# TOP.net
KiCad netlist of a schematic drawn in Altium Designer
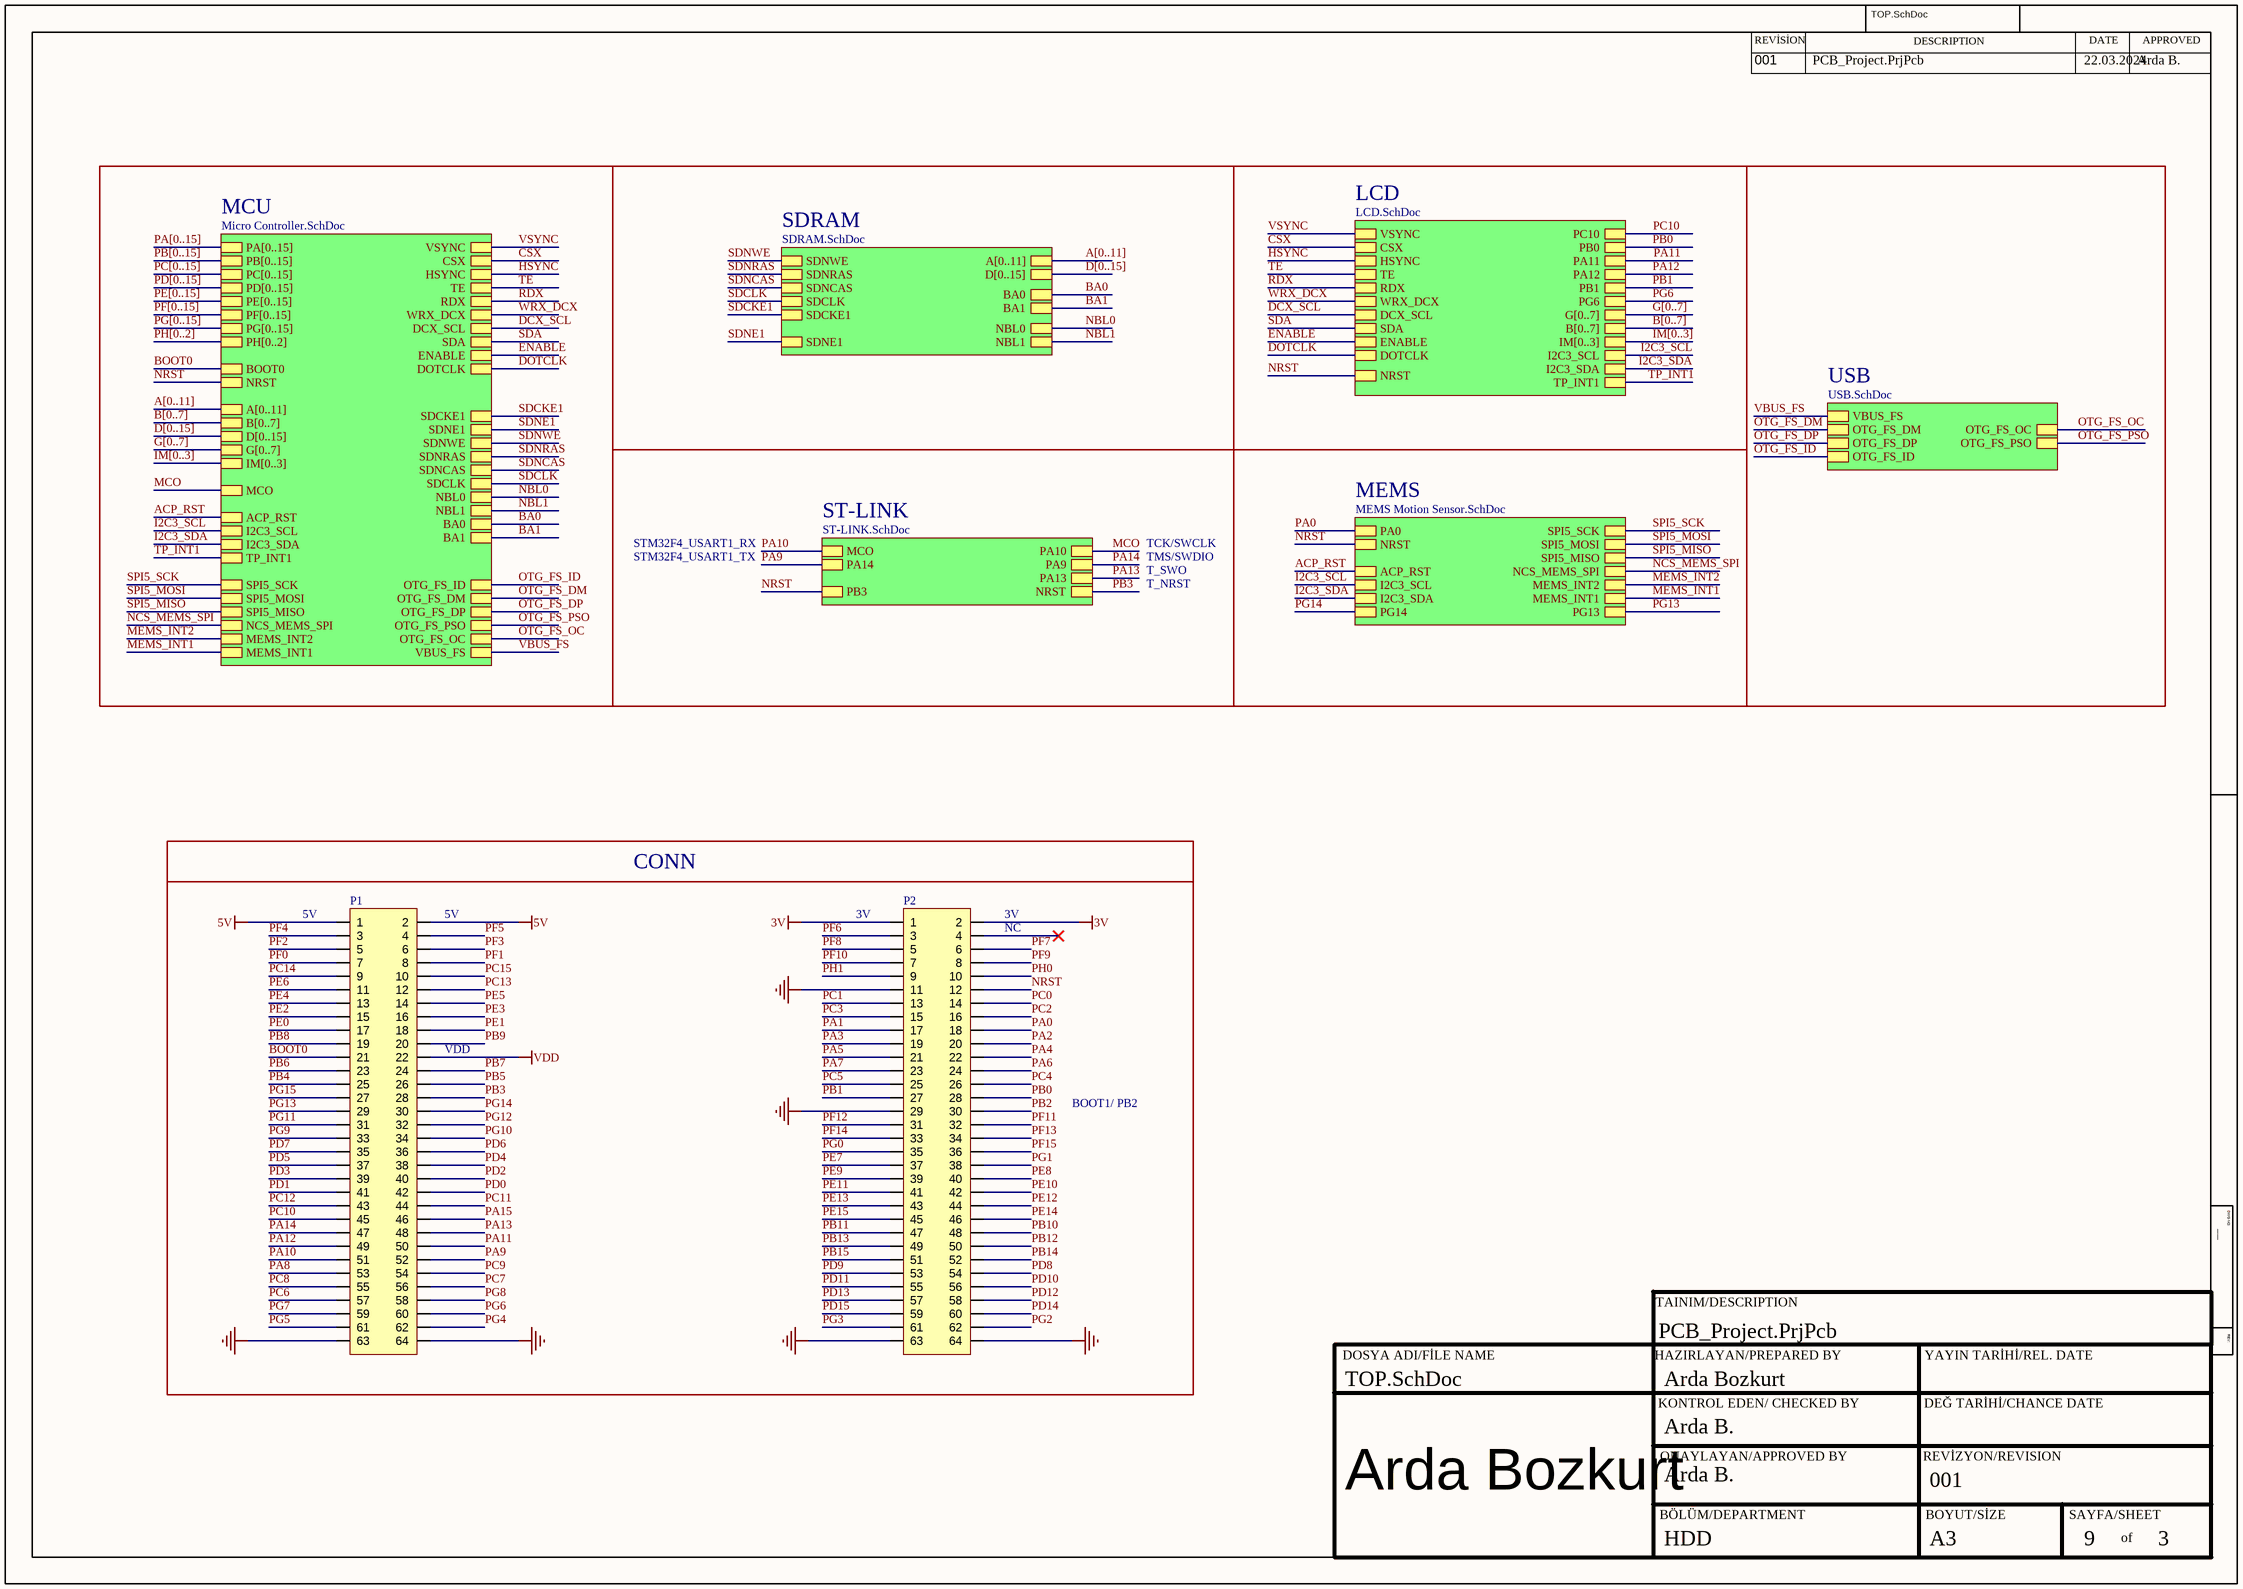
[diagram p0: TOP.SchDoc]

(export (version "E")
  (design (tool "Eeschema 10.0.6"))
  (components
    (comp (ref "P1")
      (value "TSW-132-24-T-D")
      (footprint "CONN-2*32POS")
      (description "Headers & Wire Housings Classic PCB Header Strips, 0.100 pitch")
      (fields
        (field (name "MANUFACTURER") "Wurth Electronics")
        (field (name "MANUFACTURER PART NUMBER") "61303221121")
      )
      (libsource (lib "STM32") (part "CONN HEADER VERT 32POS 2.54MM"))
    )
    (comp (ref "P2")
      (value "TSW-132-24-T-D")
      (footprint "CONN-2*32POS")
      (description "Headers & Wire Housings Classic PCB Header Strips, 0.100 pitch")
      (fields
        (field (name "MANUFACTURER") "Wurth Electronics")
        (field (name "MANUFACTURER PART NUMBER") "61303221121")
      )
      (libsource (lib "STM32") (part "CONN HEADER VERT 32POS 2.54MM"))
    )
  )
  (nets
    (net (code "54") (name "/BOOT0") (class "Default")
      (node (ref "P1") (pin "21") (pinfunction "21_21") (pintype "passive"))
    )
    (net (code "72") (name "/NRST") (class "Default")
      (node (ref "P2") (pin "12") (pinfunction "12_12") (pintype "passive"))
    )
    (net (code "78") (name "/PA0") (class "Default")
      (node (ref "P2") (pin "18") (pinfunction "18_18") (pintype "passive"))
    )
    (net (code "79") (name "/PA1") (class "Default")
      (node (ref "P2") (pin "17") (pinfunction "17_17") (pintype "passive"))
    )
    (net (code "80") (name "/PA2") (class "Default")
      (node (ref "P2") (pin "20") (pinfunction "20_20") (pintype "passive"))
    )
    (net (code "81") (name "/PA3") (class "Default")
      (node (ref "P2") (pin "19") (pinfunction "19_19") (pintype "passive"))
    )
    (net (code "82") (name "/PA4") (class "Default")
      (node (ref "P2") (pin "22") (pinfunction "22_22") (pintype "passive"))
    )
    (net (code "83") (name "/PA5") (class "Default")
      (node (ref "P2") (pin "21") (pinfunction "21_21") (pintype "passive"))
    )
    (net (code "84") (name "/PA6") (class "Default")
      (node (ref "P2") (pin "24") (pinfunction "24_24") (pintype "passive"))
    )
    (net (code "85") (name "/PA7") (class "Default")
      (node (ref "P2") (pin "23") (pinfunction "23_23") (pintype "passive"))
    )
    (net (code "86") (name "/PA8") (class "Default")
      (node (ref "P1") (pin "53") (pinfunction "53_53") (pintype "passive"))
    )
    (net (code "87") (name "/PA9") (class "Default")
      (node (ref "P1") (pin "52") (pinfunction "52_52") (pintype "passive"))
    )
    (net (code "88") (name "/PA10") (class "Default")
      (node (ref "P1") (pin "51") (pinfunction "51_51") (pintype "passive"))
    )
    (net (code "89") (name "/PA11") (class "Default")
      (node (ref "P1") (pin "50") (pinfunction "50_50") (pintype "passive"))
    )
    (net (code "90") (name "/PA12") (class "Default")
      (node (ref "P1") (pin "49") (pinfunction "49_49") (pintype "passive"))
    )
    (net (code "91") (name "/PA13") (class "Default")
      (node (ref "P1") (pin "48") (pinfunction "48_48") (pintype "passive"))
    )
    (net (code "92") (name "/PA14") (class "Default")
      (node (ref "P1") (pin "47") (pinfunction "47_47") (pintype "passive"))
    )
    (net (code "93") (name "/PA15") (class "Default")
      (node (ref "P1") (pin "46") (pinfunction "46_46") (pintype "passive"))
    )
    (net (code "95") (name "/PB0") (class "Default")
      (node (ref "P2") (pin "28") (pinfunction "28_28") (pintype "passive"))
    )
    (net (code "96") (name "/PB1") (class "Default")
      (node (ref "P2") (pin "27") (pinfunction "27_27") (pintype "passive"))
    )
    (net (code "97") (name "/PB2") (class "Default")
      (node (ref "P2") (pin "30") (pinfunction "30_30") (pintype "passive"))
    )
    (net (code "98") (name "/PB3") (class "Default")
      (node (ref "P1") (pin "28") (pinfunction "28_28") (pintype "passive"))
    )
    (net (code "99") (name "/PB4") (class "Default")
      (node (ref "P1") (pin "25") (pinfunction "25_25") (pintype "passive"))
    )
    (net (code "100") (name "/PB5") (class "Default")
      (node (ref "P1") (pin "26") (pinfunction "26_26") (pintype "passive"))
    )
    (net (code "101") (name "/PB6") (class "Default")
      (node (ref "P1") (pin "23") (pinfunction "23_23") (pintype "passive"))
    )
    (net (code "102") (name "/PB7") (class "Default")
      (node (ref "P1") (pin "24") (pinfunction "24_24") (pintype "passive"))
    )
    (net (code "103") (name "/PB8") (class "Default")
      (node (ref "P1") (pin "19") (pinfunction "19_19") (pintype "passive"))
    )
    (net (code "104") (name "/PB9") (class "Default")
      (node (ref "P1") (pin "20") (pinfunction "20_20") (pintype "passive"))
    )
    (net (code "105") (name "/PB10") (class "Default")
      (node (ref "P2") (pin "48") (pinfunction "48_48") (pintype "passive"))
    )
    (net (code "106") (name "/PB11") (class "Default")
      (node (ref "P2") (pin "47") (pinfunction "47_47") (pintype "passive"))
    )
    (net (code "107") (name "/PB12") (class "Default")
      (node (ref "P2") (pin "50") (pinfunction "50_50") (pintype "passive"))
    )
    (net (code "108") (name "/PB13") (class "Default")
      (node (ref "P2") (pin "49") (pinfunction "49_49") (pintype "passive"))
    )
    (net (code "109") (name "/PB14") (class "Default")
      (node (ref "P2") (pin "52") (pinfunction "52_52") (pintype "passive"))
    )
    (net (code "110") (name "/PB15") (class "Default")
      (node (ref "P2") (pin "51") (pinfunction "51_51") (pintype "passive"))
    )
    (net (code "112") (name "/PC0") (class "Default")
      (node (ref "P2") (pin "14") (pinfunction "14_14") (pintype "passive"))
    )
    (net (code "113") (name "/PC1") (class "Default")
      (node (ref "P2") (pin "13") (pinfunction "13_13") (pintype "passive"))
    )
    (net (code "114") (name "/PC2") (class "Default")
      (node (ref "P2") (pin "16") (pinfunction "16_16") (pintype "passive"))
    )
    (net (code "115") (name "/PC3") (class "Default")
      (node (ref "P2") (pin "15") (pinfunction "15_15") (pintype "passive"))
    )
    (net (code "116") (name "/PC4") (class "Default")
      (node (ref "P2") (pin "26") (pinfunction "26_26") (pintype "passive"))
    )
    (net (code "117") (name "/PC5") (class "Default")
      (node (ref "P2") (pin "25") (pinfunction "25_25") (pintype "passive"))
    )
    (net (code "118") (name "/PC6") (class "Default")
      (node (ref "P1") (pin "57") (pinfunction "57_57") (pintype "passive"))
    )
    (net (code "119") (name "/PC7") (class "Default")
      (node (ref "P1") (pin "56") (pinfunction "56_56") (pintype "passive"))
    )
    (net (code "120") (name "/PC8") (class "Default")
      (node (ref "P1") (pin "55") (pinfunction "55_55") (pintype "passive"))
    )
    (net (code "121") (name "/PC9") (class "Default")
      (node (ref "P1") (pin "54") (pinfunction "54_54") (pintype "passive"))
    )
    (net (code "122") (name "/PC10") (class "Default")
      (node (ref "P1") (pin "45") (pinfunction "45_45") (pintype "passive"))
    )
    (net (code "123") (name "/PC11") (class "Default")
      (node (ref "P1") (pin "44") (pinfunction "44_44") (pintype "passive"))
    )
    (net (code "124") (name "/PC12") (class "Default")
      (node (ref "P1") (pin "43") (pinfunction "43_43") (pintype "passive"))
    )
    (net (code "125") (name "/PC13") (class "Default")
      (node (ref "P1") (pin "12") (pinfunction "12_12") (pintype "passive"))
    )
    (net (code "126") (name "/PC14") (class "Default")
      (node (ref "P1") (pin "9") (pinfunction "9_9") (pintype "passive"))
    )
    (net (code "127") (name "/PC15") (class "Default")
      (node (ref "P1") (pin "10") (pinfunction "10_10") (pintype "passive"))
    )
    (net (code "129") (name "/PD0") (class "Default")
      (node (ref "P1") (pin "42") (pinfunction "42_42") (pintype "passive"))
    )
    (net (code "130") (name "/PD1") (class "Default")
      (node (ref "P1") (pin "41") (pinfunction "41_41") (pintype "passive"))
    )
    (net (code "131") (name "/PD2") (class "Default")
      (node (ref "P1") (pin "40") (pinfunction "40_40") (pintype "passive"))
    )
    (net (code "132") (name "/PD3") (class "Default")
      (node (ref "P1") (pin "39") (pinfunction "39_39") (pintype "passive"))
    )
    (net (code "133") (name "/PD4") (class "Default")
      (node (ref "P1") (pin "38") (pinfunction "38_38") (pintype "passive"))
    )
    (net (code "134") (name "/PD5") (class "Default")
      (node (ref "P1") (pin "37") (pinfunction "37_37") (pintype "passive"))
    )
    (net (code "135") (name "/PD6") (class "Default")
      (node (ref "P1") (pin "36") (pinfunction "36_36") (pintype "passive"))
    )
    (net (code "136") (name "/PD7") (class "Default")
      (node (ref "P1") (pin "35") (pinfunction "35_35") (pintype "passive"))
    )
    (net (code "137") (name "/PD8") (class "Default")
      (node (ref "P2") (pin "54") (pinfunction "54_54") (pintype "passive"))
    )
    (net (code "138") (name "/PD9") (class "Default")
      (node (ref "P2") (pin "53") (pinfunction "53_53") (pintype "passive"))
    )
    (net (code "139") (name "/PD10") (class "Default")
      (node (ref "P2") (pin "56") (pinfunction "56_56") (pintype "passive"))
    )
    (net (code "140") (name "/PD11") (class "Default")
      (node (ref "P2") (pin "55") (pinfunction "55_55") (pintype "passive"))
    )
    (net (code "141") (name "/PD12") (class "Default")
      (node (ref "P2") (pin "58") (pinfunction "58_58") (pintype "passive"))
    )
    (net (code "142") (name "/PD13") (class "Default")
      (node (ref "P2") (pin "57") (pinfunction "57_57") (pintype "passive"))
    )
    (net (code "143") (name "/PD14") (class "Default")
      (node (ref "P2") (pin "60") (pinfunction "60_60") (pintype "passive"))
    )
    (net (code "144") (name "/PD15") (class "Default")
      (node (ref "P2") (pin "59") (pinfunction "59_59") (pintype "passive"))
    )
    (net (code "146") (name "/PE0") (class "Default")
      (node (ref "P1") (pin "17") (pinfunction "17_17") (pintype "passive"))
    )
    (net (code "147") (name "/PE1") (class "Default")
      (node (ref "P1") (pin "18") (pinfunction "18_18") (pintype "passive"))
    )
    (net (code "148") (name "/PE2") (class "Default")
      (node (ref "P1") (pin "15") (pinfunction "15_15") (pintype "passive"))
    )
    (net (code "149") (name "/PE3") (class "Default")
      (node (ref "P1") (pin "16") (pinfunction "16_16") (pintype "passive"))
    )
    (net (code "150") (name "/PE4") (class "Default")
      (node (ref "P1") (pin "13") (pinfunction "13_13") (pintype "passive"))
    )
    (net (code "151") (name "/PE5") (class "Default")
      (node (ref "P1") (pin "14") (pinfunction "14_14") (pintype "passive"))
    )
    (net (code "152") (name "/PE6") (class "Default")
      (node (ref "P1") (pin "11") (pinfunction "11_11") (pintype "passive"))
    )
    (net (code "153") (name "/PE7") (class "Default")
      (node (ref "P2") (pin "37") (pinfunction "37_37") (pintype "passive"))
    )
    (net (code "154") (name "/PE8") (class "Default")
      (node (ref "P2") (pin "40") (pinfunction "40_40") (pintype "passive"))
    )
    (net (code "155") (name "/PE9") (class "Default")
      (node (ref "P2") (pin "39") (pinfunction "39_39") (pintype "passive"))
    )
    (net (code "156") (name "/PE10") (class "Default")
      (node (ref "P2") (pin "42") (pinfunction "42_42") (pintype "passive"))
    )
    (net (code "157") (name "/PE11") (class "Default")
      (node (ref "P2") (pin "41") (pinfunction "41_41") (pintype "passive"))
    )
    (net (code "158") (name "/PE12") (class "Default")
      (node (ref "P2") (pin "44") (pinfunction "44_44") (pintype "passive"))
    )
    (net (code "159") (name "/PE13") (class "Default")
      (node (ref "P2") (pin "43") (pinfunction "43_43") (pintype "passive"))
    )
    (net (code "160") (name "/PE14") (class "Default")
      (node (ref "P2") (pin "46") (pinfunction "46_46") (pintype "passive"))
    )
    (net (code "161") (name "/PE15") (class "Default")
      (node (ref "P2") (pin "45") (pinfunction "45_45") (pintype "passive"))
    )
    (net (code "163") (name "/PF0") (class "Default")
      (node (ref "P1") (pin "7") (pinfunction "7_7") (pintype "passive"))
    )
    (net (code "164") (name "/PF1") (class "Default")
      (node (ref "P1") (pin "8") (pinfunction "8_8") (pintype "passive"))
    )
    (net (code "165") (name "/PF2") (class "Default")
      (node (ref "P1") (pin "5") (pinfunction "5_5") (pintype "passive"))
    )
    (net (code "166") (name "/PF3") (class "Default")
      (node (ref "P1") (pin "6") (pinfunction "6_6") (pintype "passive"))
    )
    (net (code "167") (name "/PF4") (class "Default")
      (node (ref "P1") (pin "3") (pinfunction "3_3") (pintype "passive"))
    )
    (net (code "168") (name "/PF5") (class "Default")
      (node (ref "P1") (pin "4") (pinfunction "4_4") (pintype "passive"))
    )
    (net (code "169") (name "/PF6") (class "Default")
      (node (ref "P2") (pin "3") (pinfunction "3_3") (pintype "passive"))
    )
    (net (code "170") (name "/PF7") (class "Default")
      (node (ref "P2") (pin "6") (pinfunction "6_6") (pintype "passive"))
    )
    (net (code "171") (name "/PF8") (class "Default")
      (node (ref "P2") (pin "5") (pinfunction "5_5") (pintype "passive"))
    )
    (net (code "172") (name "/PF9") (class "Default")
      (node (ref "P2") (pin "8") (pinfunction "8_8") (pintype "passive"))
    )
    (net (code "173") (name "/PF10") (class "Default")
      (node (ref "P2") (pin "7") (pinfunction "7_7") (pintype "passive"))
    )
    (net (code "174") (name "/PF11") (class "Default")
      (node (ref "P2") (pin "32") (pinfunction "32_32") (pintype "passive"))
    )
    (net (code "175") (name "/PF12") (class "Default")
      (node (ref "P2") (pin "31") (pinfunction "31_31") (pintype "passive"))
    )
    (net (code "176") (name "/PF13") (class "Default")
      (node (ref "P2") (pin "34") (pinfunction "34_34") (pintype "passive"))
    )
    (net (code "177") (name "/PF14") (class "Default")
      (node (ref "P2") (pin "33") (pinfunction "33_33") (pintype "passive"))
    )
    (net (code "178") (name "/PF15") (class "Default")
      (node (ref "P2") (pin "36") (pinfunction "36_36") (pintype "passive"))
    )
    (net (code "180") (name "/PG0") (class "Default")
      (node (ref "P2") (pin "35") (pinfunction "35_35") (pintype "passive"))
    )
    (net (code "181") (name "/PG1") (class "Default")
      (node (ref "P2") (pin "38") (pinfunction "38_38") (pintype "passive"))
    )
    (net (code "182") (name "/PG2") (class "Default")
      (node (ref "P2") (pin "62") (pinfunction "62_62") (pintype "passive"))
    )
    (net (code "183") (name "/PG3") (class "Default")
      (node (ref "P2") (pin "61") (pinfunction "61_61") (pintype "passive"))
    )
    (net (code "184") (name "/PG4") (class "Default")
      (node (ref "P1") (pin "62") (pinfunction "62_62") (pintype "passive"))
    )
    (net (code "185") (name "/PG5") (class "Default")
      (node (ref "P1") (pin "61") (pinfunction "61_61") (pintype "passive"))
    )
    (net (code "186") (name "/PG6") (class "Default")
      (node (ref "P1") (pin "60") (pinfunction "60_60") (pintype "passive"))
    )
    (net (code "187") (name "/PG7") (class "Default")
      (node (ref "P1") (pin "59") (pinfunction "59_59") (pintype "passive"))
    )
    (net (code "188") (name "/PG8") (class "Default")
      (node (ref "P1") (pin "58") (pinfunction "58_58") (pintype "passive"))
    )
    (net (code "189") (name "/PG9") (class "Default")
      (node (ref "P1") (pin "33") (pinfunction "33_33") (pintype "passive"))
    )
    (net (code "190") (name "/PG10") (class "Default")
      (node (ref "P1") (pin "34") (pinfunction "34_34") (pintype "passive"))
    )
    (net (code "191") (name "/PG11") (class "Default")
      (node (ref "P1") (pin "31") (pinfunction "31_31") (pintype "passive"))
    )
    (net (code "192") (name "/PG12") (class "Default")
      (node (ref "P1") (pin "32") (pinfunction "32_32") (pintype "passive"))
    )
    (net (code "193") (name "/PG13") (class "Default")
      (node (ref "P1") (pin "29") (pinfunction "29_29") (pintype "passive"))
    )
    (net (code "194") (name "/PG14") (class "Default")
      (node (ref "P1") (pin "30") (pinfunction "30_30") (pintype "passive"))
    )
    (net (code "195") (name "/PG15") (class "Default")
      (node (ref "P1") (pin "27") (pinfunction "27_27") (pintype "passive"))
    )
    (net (code "197") (name "/PH0") (class "Default")
      (node (ref "P2") (pin "10") (pinfunction "10_10") (pintype "passive"))
    )
    (net (code "198") (name "/PH1") (class "Default")
      (node (ref "P2") (pin "9") (pinfunction "9_9") (pintype "passive"))
    )
    (net (code "216") (name "3V") (class "Default")
      (node (ref "P2") (pin "1") (pinfunction "1_1") (pintype "passive"))
      (node (ref "P2") (pin "2") (pinfunction "2_2") (pintype "passive"))
    )
    (net (code "217") (name "5V") (class "Default")
      (node (ref "P1") (pin "1") (pinfunction "1_1") (pintype "passive"))
      (node (ref "P1") (pin "2") (pinfunction "2_2") (pintype "passive"))
    )
    (net (code "218") (name "GND") (class "Default")
      (node (ref "P1") (pin "63") (pinfunction "63_63") (pintype "passive"))
      (node (ref "P1") (pin "64") (pinfunction "64_64") (pintype "passive"))
      (node (ref "P2") (pin "11") (pinfunction "11_11") (pintype "passive"))
      (node (ref "P2") (pin "29") (pinfunction "29_29") (pintype "passive"))
      (node (ref "P2") (pin "63") (pinfunction "63_63") (pintype "passive"))
      (node (ref "P2") (pin "64") (pinfunction "64_64") (pintype "passive"))
    )
    (net (code "219") (name "VDD") (class "Default")
      (node (ref "P1") (pin "22") (pinfunction "22_22") (pintype "passive"))
    )
    (net (code "220") (name "unconnected-(P2-Pad4)") (class "Default")
      (node (ref "P2") (pin "4") (pinfunction "4_4") (pintype "passive+no_connect"))
    )
  )
)
